# Science_Board_Top_Level.net
KiCad netlist of a schematic drawn in Altium Designer
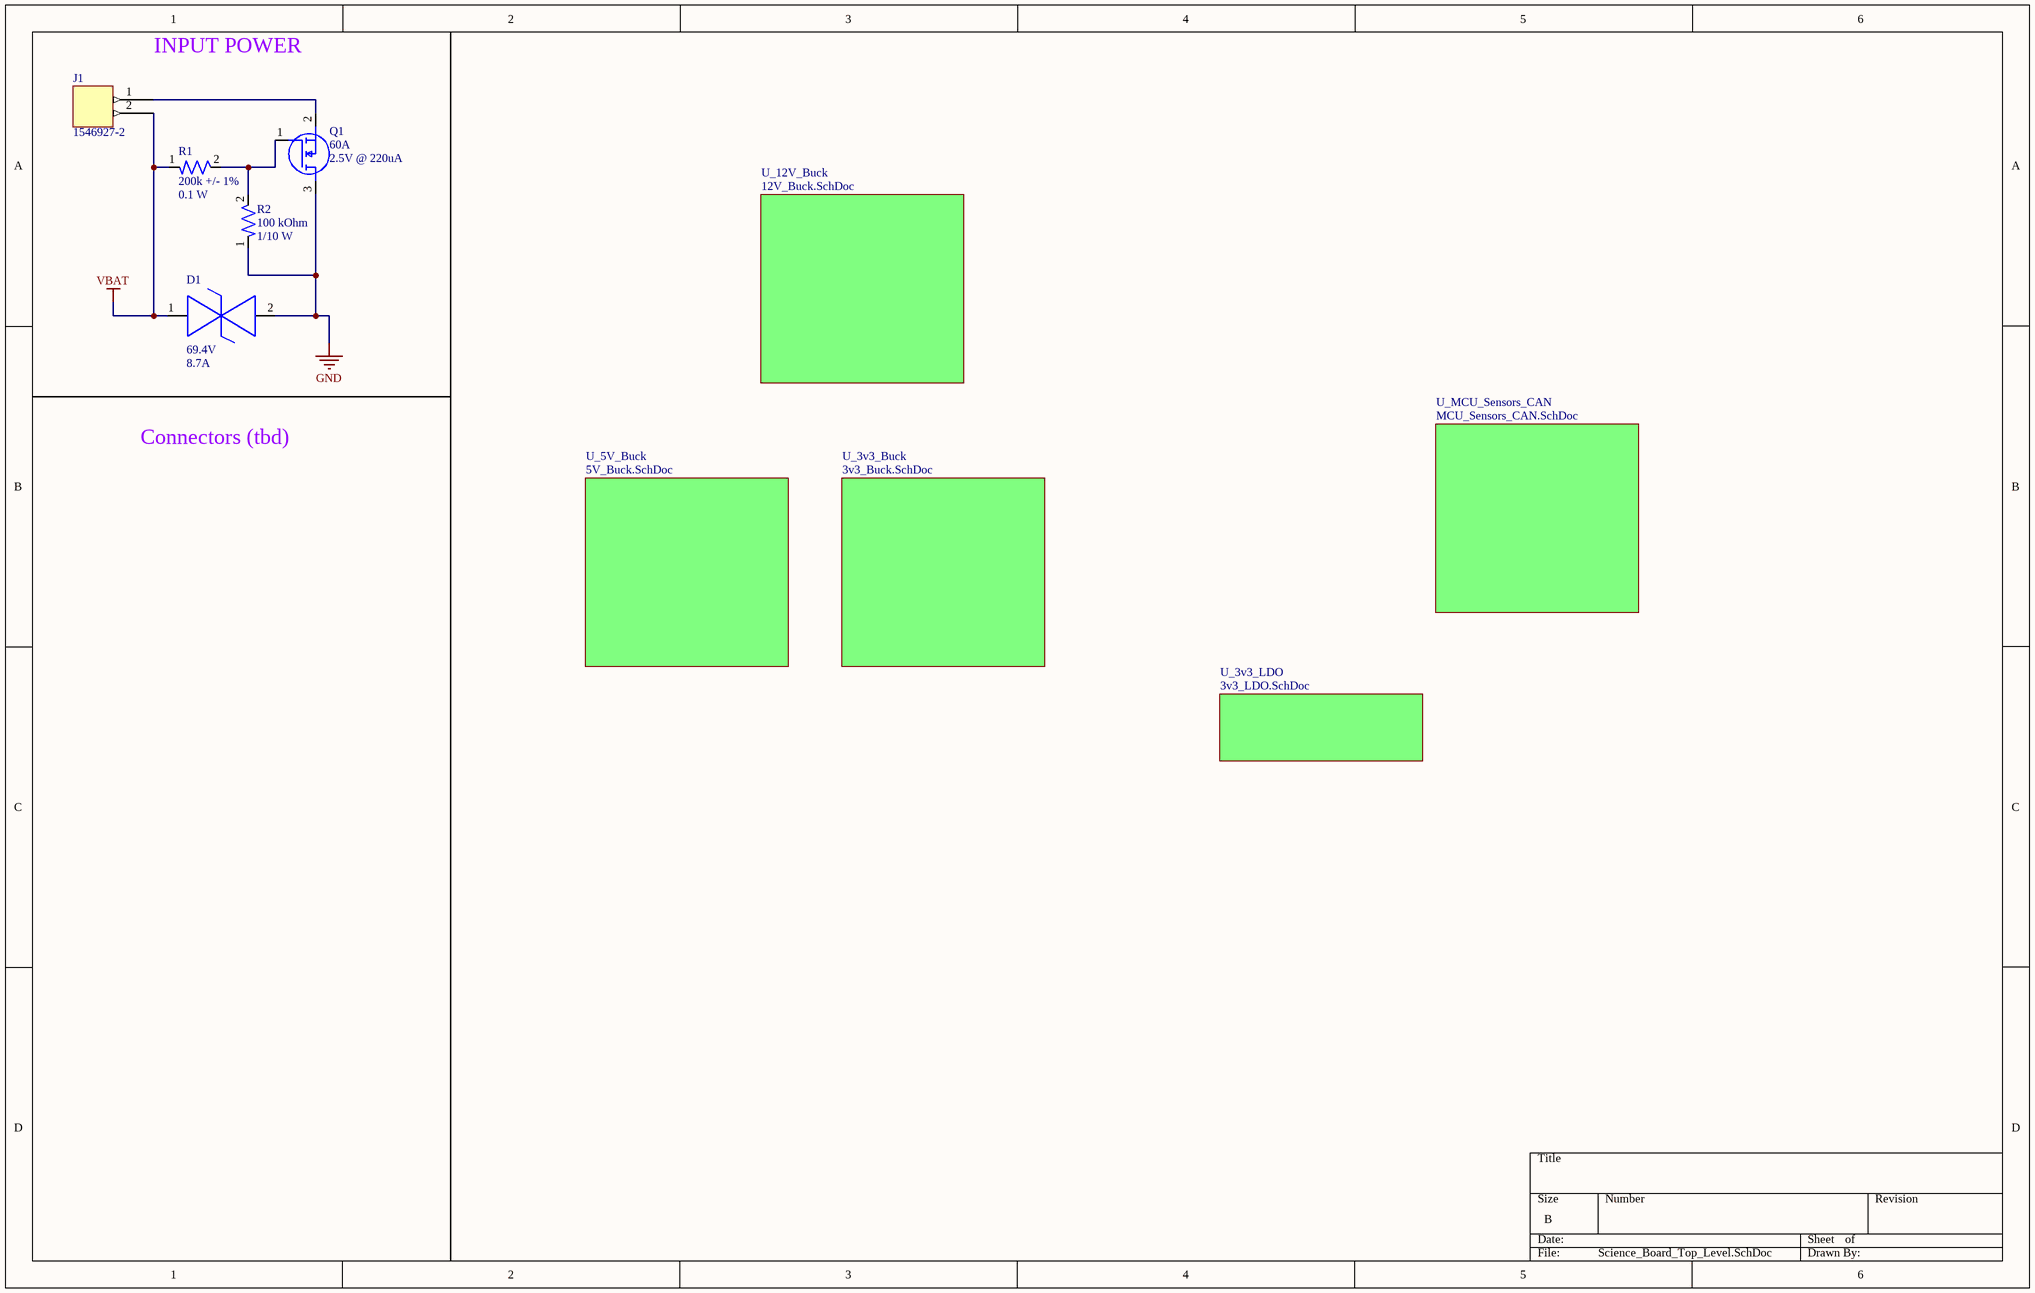
[diagram p0: Science_Board_Top_Level.SchDoc]

(export (version "E")
  (design (tool "Eeschema 10.0.6"))
  (components
    (comp (ref "D1")
      (value "SMBJE43CAH")
      (footprint "DO-214AA (SMBJ)")
      (description "69.4V Clamp 8.7A Ipp Tvs Diode Surface Mount DO-214AA (SMBJ)")
      (fields (field (name "VCLAMP") "69.4V") (field (name "PEAK PULSER CURRENT") "8.7A"))
      (libsource (lib "MasterLib") (part "DIO-69.4V-0001"))
    )
    (comp (ref "J1")
      (value "1546927-2")
      (footprint "CONN-1546927-2")
      (libsource (lib "MasterLib") (part "CON-2POS-0003"))
    )
    (comp (ref "Q1")
      (value "TPH7R006PL,L1Q")
      (footprint "NMOS-8PowerVDFN")
      (description "N-Channel 60 V 60A (Tc) 81W (Tc) Surface Mount 8-SOP Advance (5x5)")
      (fields (field (name "DRAIN CURRENT") "60A") (field (name "VGS") "2.5V @ 220uA"))
      (libsource (lib "MasterLib") (part "NMOS-60A-0001"))
    )
    (comp (ref "R1")
      (value "ERJ-3EKF2003V")
      (footprint "RES-0603")
      (description "200 kOhms ±1% 0.1W, 1/10W Chip Resistor 0603 (1608 Metric) Automotive AEC-Q200 Thick Film")
      (fields
        (field (name "MANUFACTURER") "Panasonic Electronic Components")
        (field (name "RESISTANCE") "200k +/- 1%")
        (field (name "POWER RATING") "0.1 W")
      )
      (libsource (lib "MasterLib") (part "RES-200K-0001"))
    )
    (comp (ref "R2")
      (value "RC0603FR-07100KL")
      (footprint "RES-0603")
      (description "100 kOhms ±1% 0.1W, 1/10W Chip Resistor 0603 (1608 Metric) Moisture Resistant Thick Film")
      (fields
        (field (name "TOLERANCE") "+/- 1%")
        (field (name "RESISTANCE") "100 kOhm")
        (field (name "POWER") "1/10 W")
      )
      (libsource (lib "MasterLib") (part "RES-100K-0003"))
    )
  )
  (nets
    (net (code "1") (name "GND") (class "Default")
      (node (ref "D1") (pin "2") (pintype "passive"))
      (node (ref "Q1") (pin "3") (pinfunction "D_3") (pintype "passive"))
      (node (ref "R2") (pin "1") (pinfunction "1_1") (pintype "passive"))
    )
    (net (code "2") (name "Net-(Q1-G)") (class "Default")
      (node (ref "Q1") (pin "1") (pinfunction "G_1") (pintype "passive"))
      (node (ref "R1") (pin "2") (pinfunction "2_2") (pintype "passive"))
      (node (ref "R2") (pin "2") (pinfunction "2_2") (pintype "passive"))
    )
    (net (code "3") (name "Net-(Q1-S)") (class "Default")
      (node (ref "J1") (pin "1") (pintype "output"))
      (node (ref "Q1") (pin "2") (pinfunction "S_2") (pintype "passive"))
    )
    (net (code "4") (name "VBAT") (class "Default")
      (node (ref "D1") (pin "1") (pintype "passive"))
      (node (ref "J1") (pin "2") (pintype "output"))
      (node (ref "R1") (pin "1") (pinfunction "1_1") (pintype "passive"))
    )
  )
)
